# 6_Airframe-NXP_i_MX7.net
KiCad netlist of a schematic drawn in Altium Designer
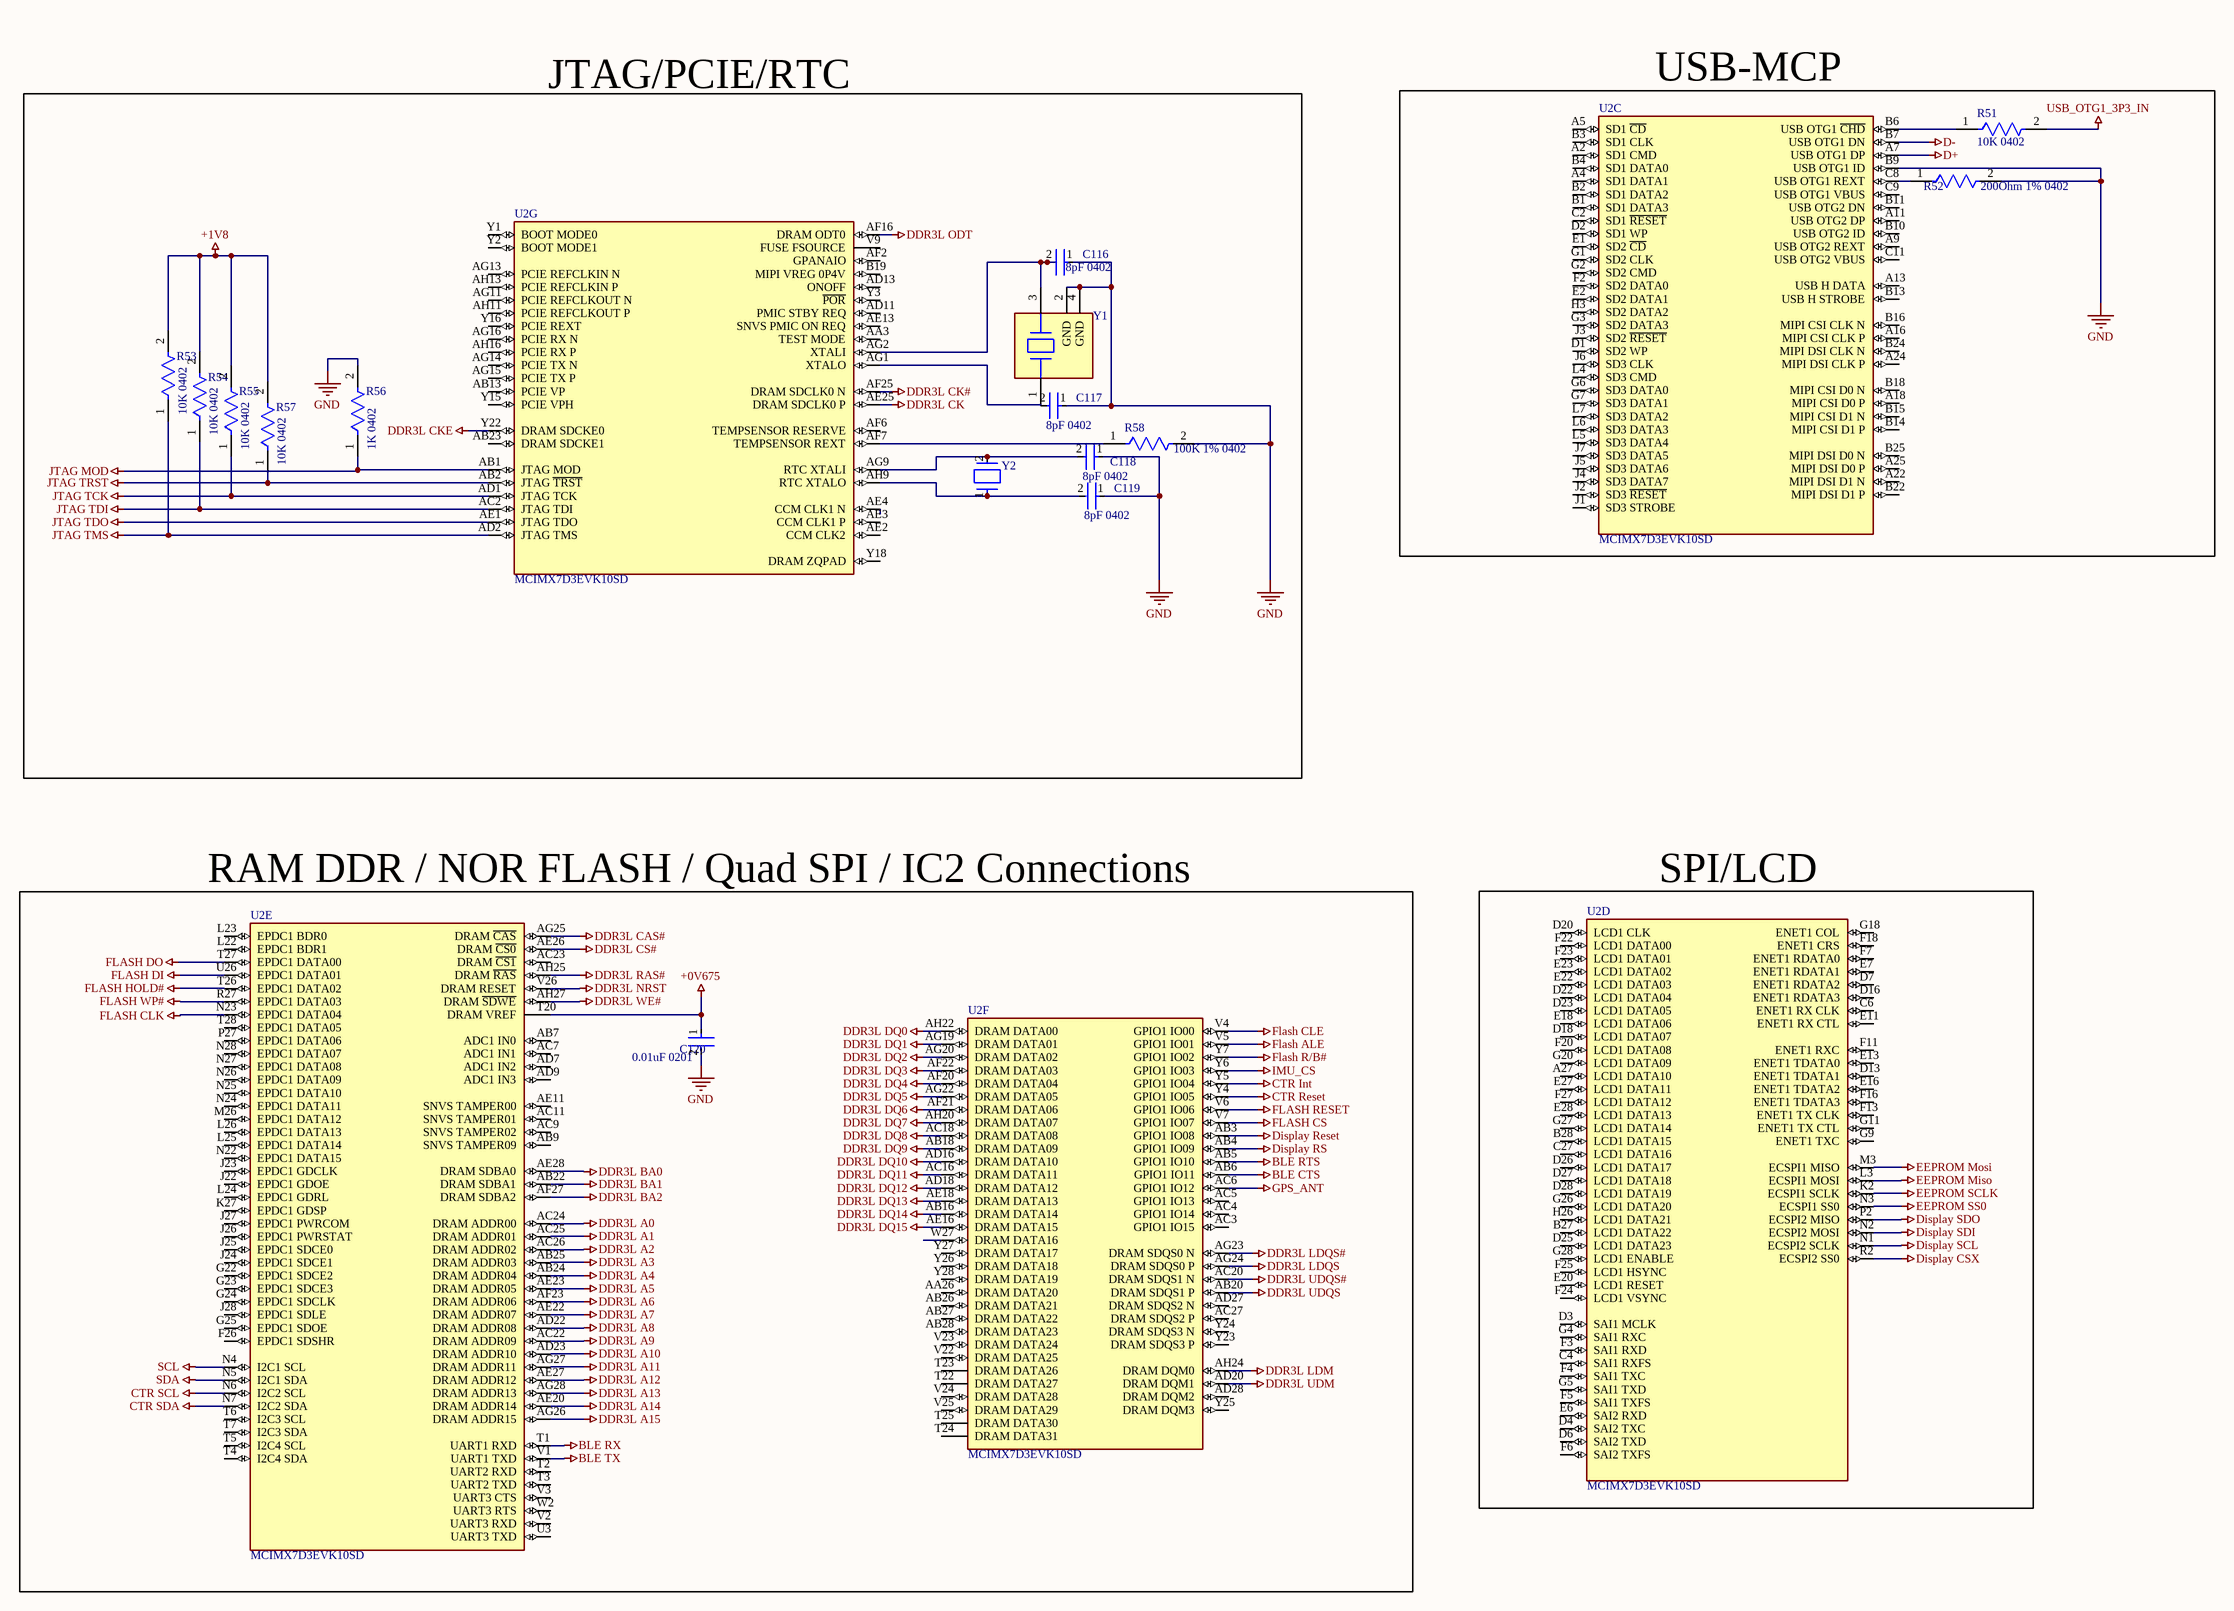
[diagram p0: 6_Airframe-NXP_i.MX7.SchDoc]

(export (version "E")
  (design (tool "Eeschema 10.0.6"))
  (components
    (comp (ref "C116")
      (value "8pF 0402")
      (footprint "FP-C0402C225M9PACTU-MFG")
      (description "CAP CER 2.2UF 6.3V X5R 0402")
      (fields (field (name "VOLTAGE") "6.3V") (field (name "TOLERANCE") "20%"))
      (libsource (lib "Altium Content Vault") (part "b4654b650e69147ec39a6b967a45e02"))
    )
    (comp (ref "C117")
      (value "8pF 0402")
      (footprint "FP-C0402C225M9PACTU-MFG")
      (description "CAP CER 2.2UF 6.3V X5R 0402")
      (fields (field (name "VOLTAGE") "6.3V") (field (name "TOLERANCE") "20%"))
      (libsource (lib "Altium Content Vault") (part "b4654b650e69147ec39a6b967a45e02"))
    )
    (comp (ref "C118")
      (value "8pF 0402")
      (footprint "FP-C0402C225M9PACTU-MFG")
      (description "CAP CER 2.2UF 6.3V X5R 0402")
      (fields (field (name "VOLTAGE") "6.3V") (field (name "TOLERANCE") "20%"))
      (libsource (lib "Altium Content Vault") (part "b4654b650e69147ec39a6b967a45e02"))
    )
    (comp (ref "C119")
      (value "8pF 0402")
      (footprint "FP-C0402C225M9PACTU-MFG")
      (description "CAP CER 2.2UF 6.3V X5R 0402")
      (fields (field (name "VOLTAGE") "6.3V") (field (name "TOLERANCE") "20%"))
      (libsource (lib "Altium Content Vault") (part "b4654b650e69147ec39a6b967a45e02"))
    )
    (comp (ref "C120")
      (value "0.01uF 0201")
      (footprint "FP-C0603-030-0_03-IPC_C")
      (description "Multilayer Ceramic Capacitors 220nF ±10% 6.3V X6S SMD 0201")
      (fields (field (name "TOLERANCE") "10%"))
      (libsource (lib "Altium Content Vault") (part "02cd4be3c70576c341d710602a673aa"))
    )
    (comp (ref "R51")
      (value "10K 0402")
      (footprint "FP-CRCW0402-e3-IPC_B")
      (description "RES SMD 10K OHM 1% 1/16W 0402")
      (fields (field (name "TOLERANCE") "1%"))
      (libsource (lib "Altium Content Vault") (part "1029c3af85768c4190bb7ad29bc67b5"))
    )
    (comp (ref "R52")
      (value "200Ohm 1% 0402")
      (footprint "FP-CRCW0402-e3-IPC_C")
      (description "RES Thick Film, 200Ω, 1%, 0.063W, 100ppm/°C, 0402")
      (fields (field (name "TOLERANCE") "1%"))
      (libsource (lib "Altium Content Vault") (part "1029c3af85768c4190bb7ad29bc67b5"))
    )
    (comp (ref "R53")
      (value "10K 0402")
      (footprint "FP-CRCW0402-e3-IPC_B")
      (description "RES SMD 10K OHM 1% 1/16W 0402")
      (fields (field (name "TOLERANCE") "1%"))
      (libsource (lib "Altium Content Vault") (part "1029c3af85768c4190bb7ad29bc67b5"))
    )
    (comp (ref "R54")
      (value "10K 0402")
      (footprint "FP-CRCW0402-e3-IPC_B")
      (description "RES SMD 10K OHM 1% 1/16W 0402")
      (fields (field (name "TOLERANCE") "1%"))
      (libsource (lib "Altium Content Vault") (part "1029c3af85768c4190bb7ad29bc67b5"))
    )
    (comp (ref "R55")
      (value "10K 0402")
      (footprint "FP-CRCW0402-e3-IPC_B")
      (description "RES SMD 10K OHM 1% 1/16W 0402")
      (fields (field (name "TOLERANCE") "1%"))
      (libsource (lib "Altium Content Vault") (part "1029c3af85768c4190bb7ad29bc67b5"))
    )
    (comp (ref "R56")
      (value "1K 0402")
      (footprint "FP-CRCW0402-e3-IPC_B")
      (description "RES SMD 10K OHM 1% 1/16W 0402")
      (fields (field (name "TOLERANCE") "1%"))
      (libsource (lib "Altium Content Vault") (part "1029c3af85768c4190bb7ad29bc67b5"))
    )
    (comp (ref "R57")
      (value "10K 0402")
      (footprint "FP-CRCW0402-e3-IPC_B")
      (description "RES SMD 10K OHM 1% 1/16W 0402")
      (fields (field (name "TOLERANCE") "1%"))
      (libsource (lib "Altium Content Vault") (part "1029c3af85768c4190bb7ad29bc67b5"))
    )
    (comp (ref "R58")
      (value "100K 1% 0402")
      (footprint "FP-CRCW0402-e3-IPC_C")
      (description "RES Thick Film, 200Ω, 1%, 0.063W, 100ppm/°C, 0402")
      (fields (field (name "TOLERANCE") "1%"))
      (libsource (lib "Altium Content Vault") (part "1029c3af85768c4190bb7ad29bc67b5"))
    )
    (comp (ref "U2")
      (value "MCIMX7D3EVK10SD")
      (footprint "FP-SOT1839-1-IPC_C")
      (description "I.MX 7DUAL: REV 1.3")
      (fields
        (field (name "MANUFACTURER") "NXP")
        (field (name "OCTOPART") "https://octopart.com/mcimx7d3evk10sd-nxp+semiconductors-84356608")
      )
      (libsource (lib "Altium Content Vault") (part "158777adc505239d6b0373594f9eb19"))
    )
    (comp (ref "Y1")
      (value "ABM8AIG-24.000MHZ-12-2Z-T3")
      (footprint "FP-ABM8AIG-MFG")
      (description "Crystal 24MHz ±20ppm (Tol) ±50ppm (Stability) 12pF FUND 50Ω Automotive 4-Pin Ultra Mini-CSMD T/R")
      (libsource (lib "Altium Content Vault") (part "5645ab55de99a04feaa93ac4102b7fe"))
    )
    (comp (ref "Y2")
      (value "ABS06-32.768KHZ-9-T")
      (footprint "FP-ABS06-MFG")
      (description "Crystal 32.768kHz ±20ppm (Tol) 9pF FUND 90kΩ 2-Pin Mini-CSMD T/R")
      (fields (field (name "TOLERANCE") "20ppm"))
      (libsource (lib "Altium Content Vault") (part "c23a69dc6c9e2f18f2079038eb95dd1"))
    )
  )
  (nets
    (net (code "1") (name "+0V675") (class "Default")
      (node (ref "C120") (pin "1") (pinfunction "1_1") (pintype "passive"))
      (node (ref "U2") (pin "T20") (pinfunction "DRAM_VREF_T20") (pintype "power_in"))
    )
    (net (code "2") (name "+1V8") (class "Default")
      (node (ref "R53") (pin "2") (pinfunction "2_2") (pintype "passive"))
      (node (ref "R54") (pin "2") (pinfunction "2_2") (pintype "passive"))
      (node (ref "R55") (pin "2") (pinfunction "2_2") (pintype "passive"))
      (node (ref "R57") (pin "2") (pinfunction "2_2") (pintype "passive"))
    )
    (net (code "3") (name "BLE CTS") (class "Default")
      (node (ref "U2") (pin "AB6") (pinfunction "GPIO1_IO11_AB6") (pintype "bidirectional"))
    )
    (net (code "4") (name "BLE RTS") (class "Default")
      (node (ref "U2") (pin "AB5") (pinfunction "GPIO1_IO10_AB5") (pintype "bidirectional"))
    )
    (net (code "5") (name "BLE RX") (class "Default")
      (node (ref "U2") (pin "T1") (pinfunction "UART1_RXD_T1") (pintype "bidirectional"))
    )
    (net (code "6") (name "BLE TX") (class "Default")
      (node (ref "U2") (pin "V1") (pinfunction "UART1_TXD_V1") (pintype "bidirectional"))
    )
    (net (code "7") (name "CTR Int") (class "Default")
      (node (ref "U2") (pin "Y5") (pinfunction "GPIO1_IO04_Y5") (pintype "bidirectional"))
    )
    (net (code "8") (name "CTR Reset") (class "Default")
      (node (ref "U2") (pin "Y4") (pinfunction "GPIO1_IO05_Y4") (pintype "bidirectional"))
    )
    (net (code "9") (name "CTR SCL") (class "Default")
      (node (ref "U2") (pin "N6") (pinfunction "I2C2_SCL_N6") (pintype "bidirectional"))
    )
    (net (code "10") (name "CTR SDA") (class "Default")
      (node (ref "U2") (pin "N7") (pinfunction "I2C2_SDA_N7") (pintype "bidirectional"))
    )
    (net (code "11") (name "D+") (class "Default")
      (node (ref "U2") (pin "A7") (pinfunction "USB_OTG1_DP_A7") (pintype "bidirectional"))
    )
    (net (code "12") (name "D-") (class "Default")
      (node (ref "U2") (pin "B7") (pinfunction "USB_OTG1_DN_B7") (pintype "bidirectional"))
    )
    (net (code "13") (name "DDR3L A0") (class "Default")
      (node (ref "U2") (pin "AC24") (pinfunction "DRAM_ADDR00_AC24") (pintype "bidirectional"))
    )
    (net (code "14") (name "DDR3L A1") (class "Default")
      (node (ref "U2") (pin "AC25") (pinfunction "DRAM_ADDR01_AC25") (pintype "bidirectional"))
    )
    (net (code "15") (name "DDR3L A2") (class "Default")
      (node (ref "U2") (pin "AC26") (pinfunction "DRAM_ADDR02_AC26") (pintype "bidirectional"))
    )
    (net (code "16") (name "DDR3L A3") (class "Default")
      (node (ref "U2") (pin "AB25") (pinfunction "DRAM_ADDR03_AB25") (pintype "bidirectional"))
    )
    (net (code "17") (name "DDR3L A4") (class "Default")
      (node (ref "U2") (pin "AB24") (pinfunction "DRAM_ADDR04_AB24") (pintype "bidirectional"))
    )
    (net (code "18") (name "DDR3L A5") (class "Default")
      (node (ref "U2") (pin "AE23") (pinfunction "DRAM_ADDR05_AE23") (pintype "bidirectional"))
    )
    (net (code "19") (name "DDR3L A6") (class "Default")
      (node (ref "U2") (pin "AF23") (pinfunction "DRAM_ADDR06_AF23") (pintype "bidirectional"))
    )
    (net (code "20") (name "DDR3L A7") (class "Default")
      (node (ref "U2") (pin "AE22") (pinfunction "DRAM_ADDR07_AE22") (pintype "bidirectional"))
    )
    (net (code "21") (name "DDR3L A8") (class "Default")
      (node (ref "U2") (pin "AD22") (pinfunction "DRAM_ADDR08_AD22") (pintype "bidirectional"))
    )
    (net (code "22") (name "DDR3L A9") (class "Default")
      (node (ref "U2") (pin "AC22") (pinfunction "DRAM_ADDR09_AC22") (pintype "bidirectional"))
    )
    (net (code "23") (name "DDR3L A10") (class "Default")
      (node (ref "U2") (pin "AD23") (pinfunction "DRAM_ADDR10_AD23") (pintype "bidirectional"))
    )
    (net (code "24") (name "DDR3L A11") (class "Default")
      (node (ref "U2") (pin "AG27") (pinfunction "DRAM_ADDR11_AG27") (pintype "bidirectional"))
    )
    (net (code "25") (name "DDR3L A12") (class "Default")
      (node (ref "U2") (pin "AE27") (pinfunction "DRAM_ADDR12_AE27") (pintype "bidirectional"))
    )
    (net (code "26") (name "DDR3L A13") (class "Default")
      (node (ref "U2") (pin "AG28") (pinfunction "DRAM_ADDR13_AG28") (pintype "bidirectional"))
    )
    (net (code "27") (name "DDR3L A14") (class "Default")
      (node (ref "U2") (pin "AE20") (pinfunction "DRAM_ADDR14_AE20") (pintype "bidirectional"))
    )
    (net (code "28") (name "DDR3L A15") (class "Default")
      (node (ref "U2") (pin "AG26") (pinfunction "DRAM_ADDR15_AG26") (pintype "bidirectional"))
    )
    (net (code "29") (name "DDR3L BA0") (class "Default")
      (node (ref "U2") (pin "AE28") (pinfunction "DRAM_SDBA0_AE28") (pintype "bidirectional"))
    )
    (net (code "30") (name "DDR3L BA1") (class "Default")
      (node (ref "U2") (pin "AB22") (pinfunction "DRAM_SDBA1_AB22") (pintype "bidirectional"))
    )
    (net (code "31") (name "DDR3L BA2") (class "Default")
      (node (ref "U2") (pin "AF27") (pinfunction "DRAM_SDBA2_AF27") (pintype "bidirectional"))
    )
    (net (code "32") (name "DDR3L CAS#") (class "Default")
      (node (ref "U2") (pin "AG25") (pinfunction "DRAM_~{CAS}_AG25") (pintype "bidirectional"))
    )
    (net (code "33") (name "DDR3L CK") (class "Default")
      (node (ref "U2") (pin "AE25") (pinfunction "DRAM_SDCLK0_P_AE25") (pintype "bidirectional"))
    )
    (net (code "34") (name "DDR3L CK#") (class "Default")
      (node (ref "U2") (pin "AF25") (pinfunction "DRAM_SDCLK0_N_AF25") (pintype "bidirectional"))
    )
    (net (code "35") (name "DDR3L CKE") (class "Default")
      (node (ref "U2") (pin "Y22") (pinfunction "DRAM_SDCKE0_Y22") (pintype "bidirectional"))
    )
    (net (code "36") (name "DDR3L CS#") (class "Default")
      (node (ref "U2") (pin "AE26") (pinfunction "DRAM_~{CS0}_AE26") (pintype "bidirectional"))
    )
    (net (code "37") (name "DDR3L DQ0") (class "Default")
      (node (ref "U2") (pin "AH22") (pinfunction "DRAM_DATA00_AH22") (pintype "bidirectional"))
    )
    (net (code "38") (name "DDR3L DQ1") (class "Default")
      (node (ref "U2") (pin "AG19") (pinfunction "DRAM_DATA01_AG19") (pintype "bidirectional"))
    )
    (net (code "39") (name "DDR3L DQ2") (class "Default")
      (node (ref "U2") (pin "AG20") (pinfunction "DRAM_DATA02_AG20") (pintype "bidirectional"))
    )
    (net (code "40") (name "DDR3L DQ3") (class "Default")
      (node (ref "U2") (pin "AF22") (pinfunction "DRAM_DATA03_AF22") (pintype "bidirectional"))
    )
    (net (code "41") (name "DDR3L DQ4") (class "Default")
      (node (ref "U2") (pin "AF20") (pinfunction "DRAM_DATA04_AF20") (pintype "bidirectional"))
    )
    (net (code "42") (name "DDR3L DQ5") (class "Default")
      (node (ref "U2") (pin "AG22") (pinfunction "DRAM_DATA05_AG22") (pintype "bidirectional"))
    )
    (net (code "43") (name "DDR3L DQ6") (class "Default")
      (node (ref "U2") (pin "AF21") (pinfunction "DRAM_DATA06_AF21") (pintype "bidirectional"))
    )
    (net (code "44") (name "DDR3L DQ7") (class "Default")
      (node (ref "U2") (pin "AH20") (pinfunction "DRAM_DATA07_AH20") (pintype "bidirectional"))
    )
    (net (code "45") (name "DDR3L DQ8") (class "Default")
      (node (ref "U2") (pin "AC18") (pinfunction "DRAM_DATA08_AC18") (pintype "bidirectional"))
    )
    (net (code "46") (name "DDR3L DQ9") (class "Default")
      (node (ref "U2") (pin "AB18") (pinfunction "DRAM_DATA09_AB18") (pintype "bidirectional"))
    )
    (net (code "47") (name "DDR3L DQ10") (class "Default")
      (node (ref "U2") (pin "AD16") (pinfunction "DRAM_DATA10_AD16") (pintype "bidirectional"))
    )
    (net (code "48") (name "DDR3L DQ11") (class "Default")
      (node (ref "U2") (pin "AC16") (pinfunction "DRAM_DATA11_AC16") (pintype "bidirectional"))
    )
    (net (code "49") (name "DDR3L DQ12") (class "Default")
      (node (ref "U2") (pin "AD18") (pinfunction "DRAM_DATA12_AD18") (pintype "bidirectional"))
    )
    (net (code "50") (name "DDR3L DQ13") (class "Default")
      (node (ref "U2") (pin "AE18") (pinfunction "DRAM_DATA13_AE18") (pintype "bidirectional"))
    )
    (net (code "51") (name "DDR3L DQ14") (class "Default")
      (node (ref "U2") (pin "AB16") (pinfunction "DRAM_DATA14_AB16") (pintype "bidirectional"))
    )
    (net (code "52") (name "DDR3L DQ15") (class "Default")
      (node (ref "U2") (pin "AE16") (pinfunction "DRAM_DATA15_AE16") (pintype "bidirectional"))
    )
    (net (code "53") (name "DDR3L LDM") (class "Default")
      (node (ref "U2") (pin "AH24") (pinfunction "DRAM_DQM0_AH24") (pintype "bidirectional"))
    )
    (net (code "54") (name "DDR3L LDQS") (class "Default")
      (node (ref "U2") (pin "AG24") (pinfunction "DRAM_SDQS0_P_AG24") (pintype "bidirectional"))
    )
    (net (code "55") (name "DDR3L LDQS#") (class "Default")
      (node (ref "U2") (pin "AG23") (pinfunction "DRAM_SDQS0_N_AG23") (pintype "bidirectional"))
    )
    (net (code "56") (name "DDR3L NRST") (class "Default")
      (node (ref "U2") (pin "V26") (pinfunction "DRAM_RESET_V26") (pintype "bidirectional"))
    )
    (net (code "57") (name "DDR3L ODT") (class "Default")
      (node (ref "U2") (pin "AF16") (pinfunction "DRAM_ODT0_AF16") (pintype "bidirectional"))
    )
    (net (code "58") (name "DDR3L RAS#") (class "Default")
      (node (ref "U2") (pin "AH25") (pinfunction "DRAM_~{RAS}_AH25") (pintype "bidirectional"))
    )
    (net (code "59") (name "DDR3L UDM") (class "Default")
      (node (ref "U2") (pin "AD20") (pinfunction "DRAM_DQM1_AD20") (pintype "bidirectional"))
    )
    (net (code "60") (name "DDR3L UDQS") (class "Default")
      (node (ref "U2") (pin "AB20") (pinfunction "DRAM_SDQS1_P_AB20") (pintype "bidirectional"))
    )
    (net (code "61") (name "DDR3L UDQS#") (class "Default")
      (node (ref "U2") (pin "AC20") (pinfunction "DRAM_SDQS1_N_AC20") (pintype "bidirectional"))
    )
    (net (code "62") (name "DDR3L WE#") (class "Default")
      (node (ref "U2") (pin "AH27") (pinfunction "DRAM_~{SDWE}_AH27") (pintype "bidirectional"))
    )
    (net (code "63") (name "Display CSX") (class "Default")
      (node (ref "U2") (pin "R2") (pinfunction "ECSPI2_SS0_R2") (pintype "bidirectional"))
    )
    (net (code "64") (name "Display RS") (class "Default")
      (node (ref "U2") (pin "AB4") (pinfunction "GPIO1_IO09_AB4") (pintype "bidirectional"))
    )
    (net (code "65") (name "Display Reset") (class "Default")
      (node (ref "U2") (pin "AB3") (pinfunction "GPIO1_IO08_AB3") (pintype "bidirectional"))
    )
    (net (code "66") (name "Display SCL") (class "Default")
      (node (ref "U2") (pin "N1") (pinfunction "ECSPI2_SCLK_N1") (pintype "bidirectional"))
    )
    (net (code "67") (name "Display SDI") (class "Default")
      (node (ref "U2") (pin "N2") (pinfunction "ECSPI2_MOSI_N2") (pintype "bidirectional"))
    )
    (net (code "68") (name "Display SDO") (class "Default")
      (node (ref "U2") (pin "P2") (pinfunction "ECSPI2_MISO_P2") (pintype "bidirectional"))
    )
    (net (code "69") (name "EEPROM Miso") (class "Default")
      (node (ref "U2") (pin "L3") (pinfunction "ECSPI1_MOSI_L3") (pintype "bidirectional"))
    )
    (net (code "70") (name "EEPROM Mosi") (class "Default")
      (node (ref "U2") (pin "M3") (pinfunction "ECSPI1_MISO_M3") (pintype "bidirectional"))
    )
    (net (code "71") (name "EEPROM SCLK") (class "Default")
      (node (ref "U2") (pin "K2") (pinfunction "ECSPI1_SCLK_K2") (pintype "bidirectional"))
    )
    (net (code "72") (name "EEPROM SS0") (class "Default")
      (node (ref "U2") (pin "N3") (pinfunction "ECSPI1_SS0_N3") (pintype "bidirectional"))
    )
    (net (code "73") (name "FLASH CLK") (class "Default")
      (node (ref "U2") (pin "N23") (pinfunction "EPDC1_DATA04_N23") (pintype "bidirectional"))
    )
    (net (code "74") (name "FLASH CS") (class "Default")
      (node (ref "U2") (pin "V7") (pinfunction "GPIO1_IO07_V7") (pintype "bidirectional"))
    )
    (net (code "75") (name "FLASH DI") (class "Default")
      (node (ref "U2") (pin "U26") (pinfunction "EPDC1_DATA01_U26") (pintype "bidirectional"))
    )
    (net (code "76") (name "FLASH DO") (class "Default")
      (node (ref "U2") (pin "T27") (pinfunction "EPDC1_DATA00_T27") (pintype "bidirectional"))
    )
    (net (code "77") (name "FLASH HOLD#") (class "Default")
      (node (ref "U2") (pin "T26") (pinfunction "EPDC1_DATA02_T26") (pintype "bidirectional"))
    )
    (net (code "78") (name "FLASH RESET") (class "Default")
      (node (ref "U2") (pin "V6") (pinfunction "GPIO1_IO06_V6") (pintype "bidirectional"))
    )
    (net (code "79") (name "FLASH WP#") (class "Default")
      (node (ref "U2") (pin "R27") (pinfunction "EPDC1_DATA03_R27") (pintype "bidirectional"))
    )
    (net (code "80") (name "Flash ALE") (class "Default")
      (node (ref "U2") (pin "V5") (pinfunction "GPIO1_IO01_V5") (pintype "bidirectional"))
    )
    (net (code "81") (name "Flash CLE") (class "Default")
      (node (ref "U2") (pin "V4") (pinfunction "GPIO1_IO00_V4") (pintype "bidirectional"))
    )
    (net (code "82") (name "Flash R{slash}B#") (class "Default")
      (node (ref "U2") (pin "Y7") (pinfunction "GPIO1_IO02_Y7") (pintype "bidirectional"))
    )
    (net (code "83") (name "GND") (class "Default")
      (node (ref "C116") (pin "1") (pinfunction "1_1") (pintype "passive"))
      (node (ref "C117") (pin "1") (pinfunction "1_1") (pintype "passive"))
      (node (ref "C118") (pin "1") (pinfunction "1_1") (pintype "passive"))
      (node (ref "C119") (pin "1") (pinfunction "1_1") (pintype "passive"))
      (node (ref "C120") (pin "2") (pinfunction "2_2") (pintype "passive"))
      (node (ref "R52") (pin "2") (pinfunction "2_2") (pintype "passive"))
      (node (ref "R56") (pin "2") (pinfunction "2_2") (pintype "passive"))
      (node (ref "R58") (pin "2") (pinfunction "2_2") (pintype "passive"))
      (node (ref "U2") (pin "B9") (pinfunction "USB_OTG1_ID_B9") (pintype "bidirectional"))
      (node (ref "Y1") (pin "2") (pinfunction "GND_2") (pintype "power_in"))
      (node (ref "Y1") (pin "4") (pinfunction "GND_4") (pintype "power_in"))
    )
    (net (code "84") (name "GPS_ANT") (class "Default")
      (node (ref "U2") (pin "AC6") (pinfunction "GPIO1_IO12_AC6") (pintype "bidirectional"))
    )
    (net (code "85") (name "IMU_CS") (class "Default")
      (node (ref "U2") (pin "Y6") (pinfunction "GPIO1_IO03_Y6") (pintype "bidirectional"))
    )
    (net (code "86") (name "JTAG MOD") (class "Default")
      (node (ref "R56") (pin "1") (pinfunction "1_1") (pintype "passive"))
      (node (ref "U2") (pin "AB1") (pinfunction "JTAG_MOD_AB1") (pintype "bidirectional"))
    )
    (net (code "87") (name "JTAG TCK") (class "Default")
      (node (ref "R55") (pin "1") (pinfunction "1_1") (pintype "passive"))
      (node (ref "U2") (pin "AD1") (pinfunction "JTAG_TCK_AD1") (pintype "bidirectional"))
    )
    (net (code "88") (name "JTAG TDI") (class "Default")
      (node (ref "R54") (pin "1") (pinfunction "1_1") (pintype "passive"))
      (node (ref "U2") (pin "AC2") (pinfunction "JTAG_TDI_AC2") (pintype "bidirectional"))
    )
    (net (code "89") (name "JTAG TDO") (class "Default")
      (node (ref "U2") (pin "AE1") (pinfunction "JTAG_TDO_AE1") (pintype "bidirectional"))
    )
    (net (code "90") (name "JTAG TMS") (class "Default")
      (node (ref "R53") (pin "1") (pinfunction "1_1") (pintype "passive"))
      (node (ref "U2") (pin "AD2") (pinfunction "JTAG_TMS_AD2") (pintype "bidirectional"))
    )
    (net (code "91") (name "JTAG TRST") (class "Default")
      (node (ref "R57") (pin "1") (pinfunction "1_1") (pintype "passive"))
      (node (ref "U2") (pin "AB2") (pinfunction "JTAG_~{TRST}_AB2") (pintype "bidirectional"))
    )
    (net (code "92") (name "Net-(U2C-USB_OTG1_REXT)") (class "Default")
      (node (ref "R52") (pin "1") (pinfunction "1_1") (pintype "passive"))
      (node (ref "U2") (pin "C8") (pinfunction "USB_OTG1_REXT_C8") (pintype "bidirectional"))
    )
    (net (code "93") (name "Net-(U2C-USB_OTG1_~{CHD})") (class "Default")
      (node (ref "R51") (pin "1") (pinfunction "1_1") (pintype "passive"))
      (node (ref "U2") (pin "B6") (pinfunction "USB_OTG1_~{CHD}_B6") (pintype "bidirectional"))
    )
    (net (code "94") (name "Net-(U2G-RTC_XTALI)") (class "Default")
      (node (ref "C118") (pin "2") (pinfunction "2_2") (pintype "passive"))
      (node (ref "U2") (pin "AG9") (pinfunction "RTC_XTALI_AG9") (pintype "bidirectional"))
      (node (ref "Y2") (pin "2") (pinfunction "2_2") (pintype "passive"))
    )
    (net (code "95") (name "Net-(U2G-RTC_XTALO)") (class "Default")
      (node (ref "C119") (pin "2") (pinfunction "2_2") (pintype "passive"))
      (node (ref "U2") (pin "AH9") (pinfunction "RTC_XTALO_AH9") (pintype "bidirectional"))
      (node (ref "Y2") (pin "1") (pinfunction "1_1") (pintype "passive"))
    )
    (net (code "96") (name "Net-(U2G-TEMPSENSOR_REXT)") (class "Default")
      (node (ref "R58") (pin "1") (pinfunction "1_1") (pintype "passive"))
      (node (ref "U2") (pin "AF7") (pinfunction "TEMPSENSOR_REXT_AF7") (pintype "bidirectional"))
    )
    (net (code "97") (name "Net-(U2G-XTALI)") (class "Default")
      (node (ref "C116") (pin "2") (pinfunction "2_2") (pintype "passive"))
      (node (ref "U2") (pin "AG2") (pinfunction "XTALI_AG2") (pintype "bidirectional"))
      (node (ref "Y1") (pin "3") (pinfunction "3_3") (pintype "passive"))
    )
    (net (code "98") (name "Net-(U2G-XTALO)") (class "Default")
      (node (ref "U2") (pin "AG1") (pinfunction "XTALO_AG1") (pintype "bidirectional"))
      (node (ref "Y1") (pin "1") (pinfunction "1_1") (pintype "passive"))
    )
    (net (code "99") (name "SCL") (class "Default")
      (node (ref "U2") (pin "N4") (pinfunction "I2C1_SCL_N4") (pintype "bidirectional"))
    )
    (net (code "100") (name "SDA") (class "Default")
      (node (ref "U2") (pin "N5") (pinfunction "I2C1_SDA_N5") (pintype "bidirectional"))
    )
    (net (code "101") (name "USB_OTG1_3P3_IN") (class "Default")
      (node (ref "R51") (pin "2") (pinfunction "2_2") (pintype "passive"))
    )
    (net (code "102") (name "unconnected-(C117-Pad2)") (class "Default")
      (node (ref "C117") (pin "2") (pinfunction "2_2") (pintype "passive"))
    )
    (net (code "103") (name "unconnected-(U2C-MIPI_CSI_CLK_N-PadB16)") (class "Default")
      (node (ref "U2") (pin "B16") (pinfunction "MIPI_CSI_CLK_N_B16") (pintype "bidirectional"))
    )
    (net (code "104") (name "unconnected-(U2C-MIPI_CSI_CLK_P-PadA16)") (class "Default")
      (node (ref "U2") (pin "A16") (pinfunction "MIPI_CSI_CLK_P_A16") (pintype "bidirectional"))
    )
    (net (code "105") (name "unconnected-(U2C-MIPI_CSI_D0_N-PadB18)") (class "Default")
      (node (ref "U2") (pin "B18") (pinfunction "MIPI_CSI_D0_N_B18") (pintype "bidirectional"))
    )
    (net (code "106") (name "unconnected-(U2C-MIPI_CSI_D0_P-PadA18)") (class "Default")
      (node (ref "U2") (pin "A18") (pinfunction "MIPI_CSI_D0_P_A18") (pintype "bidirectional"))
    )
    (net (code "107") (name "unconnected-(U2C-MIPI_CSI_D1_N-PadB15)") (class "Default")
      (node (ref "U2") (pin "B15") (pinfunction "MIPI_CSI_D1_N_B15") (pintype "bidirectional"))
    )
    (net (code "108") (name "unconnected-(U2C-MIPI_CSI_D1_P-PadB14)") (class "Default")
      (node (ref "U2") (pin "B14") (pinfunction "MIPI_CSI_D1_P_B14") (pintype "bidirectional"))
    )
    (net (code "109") (name "unconnected-(U2C-MIPI_DSI_CLK_N-PadB24)") (class "Default")
      (node (ref "U2") (pin "B24") (pinfunction "MIPI_DSI_CLK_N_B24") (pintype "bidirectional"))
    )
    (net (code "110") (name "unconnected-(U2C-MIPI_DSI_CLK_P-PadA24)") (class "Default")
      (node (ref "U2") (pin "A24") (pinfunction "MIPI_DSI_CLK_P_A24") (pintype "bidirectional"))
    )
    (net (code "111") (name "unconnected-(U2C-MIPI_DSI_D0_N-PadB25)") (class "Default")
      (node (ref "U2") (pin "B25") (pinfunction "MIPI_DSI_D0_N_B25") (pintype "bidirectional"))
    )
    (net (code "112") (name "unconnected-(U2C-MIPI_DSI_D0_P-PadA25)") (class "Default")
      (node (ref "U2") (pin "A25") (pinfunction "MIPI_DSI_D0_P_A25") (pintype "bidirectional"))
    )
    (net (code "113") (name "unconnected-(U2C-MIPI_DSI_D1_N-PadA22)") (class "Default")
      (node (ref "U2") (pin "A22") (pinfunction "MIPI_DSI_D1_N_A22") (pintype "bidirectional"))
    )
    (net (code "114") (name "unconnected-(U2C-MIPI_DSI_D1_P-PadB22)") (class "Default")
      (node (ref "U2") (pin "B22") (pinfunction "MIPI_DSI_D1_P_B22") (pintype "bidirectional"))
    )
    (net (code "115") (name "unconnected-(U2C-SD1_CLK-PadB3)") (class "Default")
      (node (ref "U2") (pin "B3") (pinfunction "SD1_CLK_B3") (pintype "bidirectional"))
    )
    (net (code "116") (name "unconnected-(U2C-SD1_CMD-PadA2)") (class "Default")
      (node (ref "U2") (pin "A2") (pinfunction "SD1_CMD_A2") (pintype "bidirectional"))
    )
    (net (code "117") (name "unconnected-(U2C-SD1_DATA0-PadB4)") (class "Default")
      (node (ref "U2") (pin "B4") (pinfunction "SD1_DATA0_B4") (pintype "bidirectional"))
    )
    (net (code "118") (name "unconnected-(U2C-SD1_DATA1-PadA4)") (class "Default")
      (node (ref "U2") (pin "A4") (pinfunction "SD1_DATA1_A4") (pintype "bidirectional"))
    )
    (net (code "119") (name "unconnected-(U2C-SD1_DATA2-PadB2)") (class "Default")
      (node (ref "U2") (pin "B2") (pinfunction "SD1_DATA2_B2") (pintype "bidirectional"))
    )
    (net (code "120") (name "unconnected-(U2C-SD1_DATA3-PadB1)") (class "Default")
      (node (ref "U2") (pin "B1") (pinfunction "SD1_DATA3_B1") (pintype "bidirectional"))
    )
    (net (code "121") (name "unconnected-(U2C-SD1_WP-PadD2)") (class "Default")
      (node (ref "U2") (pin "D2") (pinfunction "SD1_WP_D2") (pintype "bidirectional"))
    )
    (net (code "122") (name "unconnected-(U2C-SD1_~{CD}-PadA5)") (class "Default")
      (node (ref "U2") (pin "A5") (pinfunction "SD1_~{CD}_A5") (pintype "bidirectional"))
    )
    (net (code "123") (name "unconnected-(U2C-SD1_~{RESET}-PadC2)") (class "Default")
      (node (ref "U2") (pin "C2") (pinfunction "SD1_~{RESET}_C2") (pintype "bidirectional"))
    )
    (net (code "124") (name "unconnected-(U2C-SD2_CLK-PadG1)") (class "Default")
      (node (ref "U2") (pin "G1") (pinfunction "SD2_CLK_G1") (pintype "bidirectional"))
    )
    (net (code "125") (name "unconnected-(U2C-SD2_CMD-PadG2)") (class "Default")
      (node (ref "U2") (pin "G2") (pinfunction "SD2_CMD_G2") (pintype "bidirectional"))
    )
    (net (code "126") (name "unconnected-(U2C-SD2_DATA0-PadF2)") (class "Default")
      (node (ref "U2") (pin "F2") (pinfunction "SD2_DATA0_F2") (pintype "bidirectional"))
    )
    (net (code "127") (name "unconnected-(U2C-SD2_DATA1-PadE2)") (class "Default")
      (node (ref "U2") (pin "E2") (pinfunction "SD2_DATA1_E2") (pintype "bidirectional"))
    )
    (net (code "128") (name "unconnected-(U2C-SD2_DATA2-PadH3)") (class "Default")
      (node (ref "U2") (pin "H3") (pinfunction "SD2_DATA2_H3") (pintype "bidirectional"))
    )
    (net (code "129") (name "unconnected-(U2C-SD2_DATA3-PadG3)") (class "Default")
      (node (ref "U2") (pin "G3") (pinfunction "SD2_DATA3_G3") (pintype "bidirectional"))
    )
    (net (code "130") (name "unconnected-(U2C-SD2_WP-PadD1)") (class "Default")
      (node (ref "U2") (pin "D1") (pinfunction "SD2_WP_D1") (pintype "bidirectional"))
    )
    (net (code "131") (name "unconnected-(U2C-SD2_~{CD}-PadE1)") (class "Default")
      (node (ref "U2") (pin "E1") (pinfunction "SD2_~{CD}_E1") (pintype "bidirectional"))
    )
    (net (code "132") (name "unconnected-(U2C-SD2_~{RESET}-PadJ3)") (class "Default")
      (node (ref "U2") (pin "J3") (pinfunction "SD2_~{RESET}_J3") (pintype "bidirectional"))
    )
    (net (code "133") (name "unconnected-(U2C-SD3_CLK-PadJ6)") (class "Default")
      (node (ref "U2") (pin "J6") (pinfunction "SD3_CLK_J6") (pintype "bidirectional"))
    )
    (net (code "134") (name "unconnected-(U2C-SD3_CMD-PadL4)") (class "Default")
      (node (ref "U2") (pin "L4") (pinfunction "SD3_CMD_L4") (pintype "bidirectional"))
    )
    (net (code "135") (name "unconnected-(U2C-SD3_DATA0-PadG6)") (class "Default")
      (node (ref "U2") (pin "G6") (pinfunction "SD3_DATA0_G6") (pintype "bidirectional"))
    )
    (net (code "136") (name "unconnected-(U2C-SD3_DATA1-PadG7)") (class "Default")
      (node (ref "U2") (pin "G7") (pinfunction "SD3_DATA1_G7") (pintype "bidirectional"))
    )
    (net (code "137") (name "unconnected-(U2C-SD3_DATA2-PadL7)") (class "Default")
      (node (ref "U2") (pin "L7") (pinfunction "SD3_DATA2_L7") (pintype "bidirectional"))
    )
    (net (code "138") (name "unconnected-(U2C-SD3_DATA3-PadL6)") (class "Default")
      (node (ref "U2") (pin "L6") (pinfunction "SD3_DATA3_L6") (pintype "bidirectional"))
    )
    (net (code "139") (name "unconnected-(U2C-SD3_DATA4-PadL5)") (class "Default")
      (node (ref "U2") (pin "L5") (pinfunction "SD3_DATA4_L5") (pintype "bidirectional"))
    )
    (net (code "140") (name "unconnected-(U2C-SD3_DATA5-PadJ7)") (class "Default")
      (node (ref "U2") (pin "J7") (pinfunction "SD3_DATA5_J7") (pintype "bidirectional"))
    )
    (net (code "141") (name "unconnected-(U2C-SD3_DATA6-PadJ5)") (class "Default")
      (node (ref "U2") (pin "J5") (pinfunction "SD3_DATA6_J5") (pintype "bidirectional"))
    )
    (net (code "142") (name "unconnected-(U2C-SD3_DATA7-PadJ4)") (class "Default")
      (node (ref "U2") (pin "J4") (pinfunction "SD3_DATA7_J4") (pintype "bidirectional"))
    )
    (net (code "143") (name "unconnected-(U2C-SD3_STROBE-PadJ1)") (class "Default")
      (node (ref "U2") (pin "J1") (pinfunction "SD3_STROBE_J1") (pintype "bidirectional"))
    )
    (net (code "144") (name "unconnected-(U2C-SD3_~{RESET}-PadJ2)") (class "Default")
      (node (ref "U2") (pin "J2") (pinfunction "SD3_~{RESET}_J2") (pintype "bidirectional"))
    )
    (net (code "145") (name "unconnected-(U2C-USB_H_DATA-PadA13)") (class "Default")
      (node (ref "U2") (pin "A13") (pinfunction "USB_H_DATA_A13") (pintype "bidirectional"))
    )
    (net (code "146") (name "unconnected-(U2C-USB_H_STROBE-PadB13)") (class "Default")
      (node (ref "U2") (pin "B13") (pinfunction "USB_H_STROBE_B13") (pintype "bidirectional"))
    )
    (net (code "147") (name "unconnected-(U2C-USB_OTG1_VBUS-PadC9)") (class "Default")
      (node (ref "U2") (pin "C9") (pinfunction "USB_OTG1_VBUS_C9") (pintype "bidirectional"))
    )
    (net (code "148") (name "unconnected-(U2C-USB_OTG2_DN-PadB11)") (class "Default")
      (node (ref "U2") (pin "B11") (pinfunction "USB_OTG2_DN_B11") (pintype "bidirectional"))
    )
    (net (code "149") (name "unconnected-(U2C-USB_OTG2_DP-PadA11)") (class "Default")
      (node (ref "U2") (pin "A11") (pinfunction "USB_OTG2_DP_A11") (pintype "bidirectional"))
    )
    (net (code "150") (name "unconnected-(U2C-USB_OTG2_ID-PadB10)") (class "Default")
      (node (ref "U2") (pin "B10") (pinfunction "USB_OTG2_ID_B10") (pintype "bidirectional"))
    )
    (net (code "151") (name "unconnected-(U2C-USB_OTG2_REXT-PadA9)") (class "Default")
      (node (ref "U2") (pin "A9") (pinfunction "USB_OTG2_REXT_A9") (pintype "bidirectional"))
    )
    (net (code "152") (name "unconnected-(U2C-USB_OTG2_VBUS-PadC11)") (class "Default")
      (node (ref "U2") (pin "C11") (pinfunction "USB_OTG2_VBUS_C11") (pintype "bidirectional"))
    )
    (net (code "153") (name "unconnected-(U2D-ENET1_COL-PadG18)") (class "Default")
      (node (ref "U2") (pin "G18") (pinfunction "ENET1_COL_G18") (pintype "bidirectional"))
    )
    (net (code "154") (name "unconnected-(U2D-ENET1_CRS-PadF18)") (class "Default")
      (node (ref "U2") (pin "F18") (pinfunction "ENET1_CRS_F18") (pintype "bidirectional"))
    )
    (net (code "155") (name "unconnected-(U2D-ENET1_RDATA0-PadF7)") (class "Default")
      (node (ref "U2") (pin "F7") (pinfunction "ENET1_RDATA0_F7") (pintype "bidirectional"))
    )
    (net (code "156") (name "unconnected-(U2D-ENET1_RDATA1-PadE7)") (class "Default")
      (node (ref "U2") (pin "E7") (pinfunction "ENET1_RDATA1_E7") (pintype "bidirectional"))
    )
    (net (code "157") (name "unconnected-(U2D-ENET1_RDATA2-PadD7)") (class "Default")
      (node (ref "U2") (pin "D7") (pinfunction "ENET1_RDATA2_D7") (pintype "bidirectional"))
    )
    (net (code "158") (name "unconnected-(U2D-ENET1_RDATA3-PadD16)") (class "Default")
      (node (ref "U2") (pin "D16") (pinfunction "ENET1_RDATA3_D16") (pintype "bidirectional"))
    )
    (net (code "159") (name "unconnected-(U2D-ENET1_RXC-PadF11)") (class "Default")
      (node (ref "U2") (pin "F11") (pinfunction "ENET1_RXC_F11") (pintype "bidirectional"))
    )
    (net (code "160") (name "unconnected-(U2D-ENET1_RX_CLK-PadC6)") (class "Default")
      (node (ref "U2") (pin "C6") (pinfunction "ENET1_RX_CLK_C6") (pintype "bidirectional"))
    )
    (net (code "161") (name "unconnected-(U2D-ENET1_RX_CTL-PadE11)") (class "Default")
      (node (ref "U2") (pin "E11") (pinfunction "ENET1_RX_CTL_E11") (pintype "bidirectional"))
    )
    (net (code "162") (name "unconnected-(U2D-ENET1_TDATA0-PadE13)") (class "Default")
      (node (ref "U2") (pin "E13") (pinfunction "ENET1_TDATA0_E13") (pintype "bidirectional"))
    )
    (net (code "163") (name "unconnected-(U2D-ENET1_TDATA1-PadD13)") (class "Default")
      (node (ref "U2") (pin "D13") (pinfunction "ENET1_TDATA1_D13") (pintype "bidirectional"))
    )
    (net (code "164") (name "unconnected-(U2D-ENET1_TDATA2-PadE16)") (class "Default")
      (node (ref "U2") (pin "E16") (pinfunction "ENET1_TDATA2_E16") (pintype "bidirectional"))
    )
    (net (code "165") (name "unconnected-(U2D-ENET1_TDATA3-PadF16)") (class "Default")
      (node (ref "U2") (pin "F16") (pinfunction "ENET1_TDATA3_F16") (pintype "bidirectional"))
    )
    (net (code "166") (name "unconnected-(U2D-ENET1_TXC-PadG9)") (class "Default")
      (node (ref "U2") (pin "G9") (pinfunction "ENET1_TXC_G9") (pintype "bidirectional"))
    )
    (net (code "167") (name "unconnected-(U2D-ENET1_TX_CLK-PadF13)") (class "Default")
      (node (ref "U2") (pin "F13") (pinfunction "ENET1_TX_CLK_F13") (pintype "bidirectional"))
    )
    (net (code "168") (name "unconnected-(U2D-ENET1_TX_CTL-PadG11)") (class "Default")
      (node (ref "U2") (pin "G11") (pinfunction "ENET1_TX_CTL_G11") (pintype "bidirectional"))
    )
    (net (code "169") (name "unconnected-(U2D-LCD1_CLK-PadD20)") (class "Default")
      (node (ref "U2") (pin "D20") (pinfunction "LCD1_CLK_D20") (pintype "bidirectional"))
    )
    (net (code "170") (name "unconnected-(U2D-LCD1_DATA00-PadF22)") (class "Default")
      (node (ref "U2") (pin "F22") (pinfunction "LCD1_DATA00_F22") (pintype "bidirectional"))
    )
    (net (code "171") (name "unconnected-(U2D-LCD1_DATA01-PadF23)") (class "Default")
      (node (ref "U2") (pin "F23") (pinfunction "LCD1_DATA01_F23") (pintype "bidirectional"))
    )
    (net (code "172") (name "unconnected-(U2D-LCD1_DATA02-PadE23)") (class "Default")
      (node (ref "U2") (pin "E23") (pinfunction "LCD1_DATA02_E23") (pintype "bidirectional"))
    )
    (net (code "173") (name "unconnected-(U2D-LCD1_DATA03-PadE22)") (class "Default")
      (node (ref "U2") (pin "E22") (pinfunction "LCD1_DATA03_E22") (pintype "bidirectional"))
    )
    (net (code "174") (name "unconnected-(U2D-LCD1_DATA04-PadD22)") (class "Default")
      (node (ref "U2") (pin "D22") (pinfunction "LCD1_DATA04_D22") (pintype "bidirectional"))
    )
    (net (code "175") (name "unconnected-(U2D-LCD1_DATA05-PadD23)") (class "Default")
      (node (ref "U2") (pin "D23") (pinfunction "LCD1_DATA05_D23") (pintype "bidirectional"))
    )
    (net (code "176") (name "unconnected-(U2D-LCD1_DATA06-PadE18)") (class "Default")
      (node (ref "U2") (pin "E18") (pinfunction "LCD1_DATA06_E18") (pintype "bidirectional"))
    )
    (net (code "177") (name "unconnected-(U2D-LCD1_DATA07-PadD18)") (class "Default")
      (node (ref "U2") (pin "D18") (pinfunction "LCD1_DATA07_D18") (pintype "bidirectional"))
    )
    (net (code "178") (name "unconnected-(U2D-LCD1_DATA08-PadF20)") (class "Default")
      (node (ref "U2") (pin "F20") (pinfunction "LCD1_DATA08_F20") (pintype "bidirectional"))
    )
    (net (code "179") (name "unconnected-(U2D-LCD1_DATA09-PadG20)") (class "Default")
      (node (ref "U2") (pin "G20") (pinfunction "LCD1_DATA09_G20") (pintype "bidirectional"))
    )
    (net (code "180") (name "unconnected-(U2D-LCD1_DATA10-PadA27)") (class "Default")
      (node (ref "U2") (pin "A27") (pinfunction "LCD1_DATA10_A27") (pintype "bidirectional"))
    )
    (net (code "181") (name "unconnected-(U2D-LCD1_DATA11-PadE27)") (class "Default")
      (node (ref "U2") (pin "E27") (pinfunction "LCD1_DATA11_E27") (pintype "bidirectional"))
    )
    (net (code "182") (name "unconnected-(U2D-LCD1_DATA12-PadF27)") (class "Default")
      (node (ref "U2") (pin "F27") (pinfunction "LCD1_DATA12_F27") (pintype "bidirectional"))
    )
    (net (code "183") (name "unconnected-(U2D-LCD1_DATA13-PadE28)") (class "Default")
      (node (ref "U2") (pin "E28") (pinfunction "LCD1_DATA13_E28") (pintype "bidirectional"))
    )
    (net (code "184") (name "unconnected-(U2D-LCD1_DATA14-PadG27)") (class "Default")
      (node (ref "U2") (pin "G27") (pinfunction "LCD1_DATA14_G27") (pintype "bidirectional"))
    )
    (net (code "185") (name "unconnected-(U2D-LCD1_DATA15-PadB28)") (class "Default")
      (node (ref "U2") (pin "B28") (pinfunction "LCD1_DATA15_B28") (pintype "bidirectional"))
    )
    (net (code "186") (name "unconnected-(U2D-LCD1_DATA16-PadC27)") (class "Default")
      (node (ref "U2") (pin "C27") (pinfunction "LCD1_DATA16_C27") (pintype "bidirectional"))
    )
    (net (code "187") (name "unconnected-(U2D-LCD1_DATA17-PadD26)") (class "Default")
      (node (ref "U2") (pin "D26") (pinfunction "LCD1_DATA17_D26") (pintype "bidirectional"))
    )
    (net (code "188") (name "unconnected-(U2D-LCD1_DATA18-PadD27)") (class "Default")
      (node (ref "U2") (pin "D27") (pinfunction "LCD1_DATA18_D27") (pintype "bidirectional"))
    )
    (net (code "189") (name "unconnected-(U2D-LCD1_DATA19-PadD28)") (class "Default")
      (node (ref "U2") (pin "D28") (pinfunction "LCD1_DATA19_D28") (pintype "bidirectional"))
    )
    (net (code "190") (name "unconnected-(U2D-LCD1_DATA20-PadG26)") (class "Default")
      (node (ref "U2") (pin "G26") (pinfunction "LCD1_DATA20_G26") (pintype "bidirectional"))
    )
    (net (code "191") (name "unconnected-(U2D-LCD1_DATA21-PadH26)") (class "Default")
      (node (ref "U2") (pin "H26") (pinfunction "LCD1_DATA21_H26") (pintype "bidirectional"))
    )
    (net (code "192") (name "unconnected-(U2D-LCD1_DATA22-PadB27)") (class "Default")
      (node (ref "U2") (pin "B27") (pinfunction "LCD1_DATA22_B27") (pintype "bidirectional"))
    )
    (net (code "193") (name "unconnected-(U2D-LCD1_DATA23-PadD25)") (class "Default")
      (node (ref "U2") (pin "D25") (pinfunction "LCD1_DATA23_D25") (pintype "bidirectional"))
    )
    (net (code "194") (name "unconnected-(U2D-LCD1_ENABLE-PadG28)") (class "Default")
      (node (ref "U2") (pin "G28") (pinfunction "LCD1_ENABLE_G28") (pintype "bidirectional"))
    )
    (net (code "195") (name "unconnected-(U2D-LCD1_HSYNC-PadF25)") (class "Default")
      (node (ref "U2") (pin "F25") (pinfunction "LCD1_HSYNC_F25") (pintype "bidirectional"))
    )
    (net (code "196") (name "unconnected-(U2D-LCD1_RESET-PadE20)") (class "Default")
      (node (ref "U2") (pin "E20") (pinfunction "LCD1_RESET_E20") (pintype "bidirectional"))
    )
    (net (code "197") (name "unconnected-(U2D-LCD1_VSYNC-PadF24)") (class "Default")
      (node (ref "U2") (pin "F24") (pinfunction "LCD1_VSYNC_F24") (pintype "bidirectional"))
    )
    (net (code "198") (name "unconnected-(U2D-SAI1_MCLK-PadD3)") (class "Default")
      (node (ref "U2") (pin "D3") (pinfunction "SAI1_MCLK_D3") (pintype "bidirectional"))
    )
    (net (code "199") (name "unconnected-(U2D-SAI1_RXC-PadG4)") (class "Default")
      (node (ref "U2") (pin "G4") (pinfunction "SAI1_RXC_G4") (pintype "bidirectional"))
    )
    (net (code "200") (name "unconnected-(U2D-SAI1_RXD-PadF3)") (class "Default")
      (node (ref "U2") (pin "F3") (pinfunction "SAI1_RXD_F3") (pintype "bidirectional"))
    )
    (net (code "201") (name "unconnected-(U2D-SAI1_RXFS-PadC4)") (class "Default")
      (node (ref "U2") (pin "C4") (pinfunction "SAI1_RXFS_C4") (pintype "bidirectional"))
    )
    (net (code "202") (name "unconnected-(U2D-SAI1_TXC-PadF4)") (class "Default")
      (node (ref "U2") (pin "F4") (pinfunction "SAI1_TXC_F4") (pintype "bidirectional"))
    )
    (net (code "203") (name "unconnected-(U2D-SAI1_TXD-PadG5)") (class "Default")
      (node (ref "U2") (pin "G5") (pinfunction "SAI1_TXD_G5") (pintype "bidirectional"))
    )
    (net (code "204") (name "unconnected-(U2D-SAI1_TXFS-PadF5)") (class "Default")
      (node (ref "U2") (pin "F5") (pinfunction "SAI1_TXFS_F5") (pintype "bidirectional"))
    )
    (net (code "205") (name "unconnected-(U2D-SAI2_RXD-PadE6)") (class "Default")
      (node (ref "U2") (pin "E6") (pinfunction "SAI2_RXD_E6") (pintype "bidirectional"))
    )
    (net (code "206") (name "unconnected-(U2D-SAI2_TXC-PadD4)") (class "Default")
      (node (ref "U2") (pin "D4") (pinfunction "SAI2_TXC_D4") (pintype "bidirectional"))
    )
    (net (code "207") (name "unconnected-(U2D-SAI2_TXD-PadD6)") (class "Default")
      (node (ref "U2") (pin "D6") (pinfunction "SAI2_TXD_D6") (pintype "bidirectional"))
    )
    (net (code "208") (name "unconnected-(U2D-SAI2_TXFS-PadF6)") (class "Default")
      (node (ref "U2") (pin "F6") (pinfunction "SAI2_TXFS_F6") (pintype "bidirectional"))
    )
    (net (code "209") (name "unconnected-(U2E-ADC1_IN0-PadAB7)") (class "Default")
      (node (ref "U2") (pin "AB7") (pinfunction "ADC1_IN0_AB7") (pintype "bidirectional"))
    )
    (net (code "210") (name "unconnected-(U2E-ADC1_IN1-PadAC7)") (class "Default")
      (node (ref "U2") (pin "AC7") (pinfunction "ADC1_IN1_AC7") (pintype "bidirectional"))
    )
    (net (code "211") (name "unconnected-(U2E-ADC1_IN2-PadAD7)") (class "Default")
      (node (ref "U2") (pin "AD7") (pinfunction "ADC1_IN2_AD7") (pintype "bidirectional"))
    )
    (net (code "212") (name "unconnected-(U2E-ADC1_IN3-PadAD9)") (class "Default")
      (node (ref "U2") (pin "AD9") (pinfunction "ADC1_IN3_AD9") (pintype "bidirectional"))
    )
    (net (code "213") (name "unconnected-(U2E-DRAM_~{CS1}-PadAC23)") (class "Default")
      (node (ref "U2") (pin "AC23") (pinfunction "DRAM_~{CS1}_AC23") (pintype "bidirectional"))
    )
    (net (code "214") (name "unconnected-(U2E-EPDC1_BDR0-PadL23)") (class "Default")
      (node (ref "U2") (pin "L23") (pinfunction "EPDC1_BDR0_L23") (pintype "bidirectional"))
    )
    (net (code "215") (name "unconnected-(U2E-EPDC1_BDR1-PadL22)") (class "Default")
      (node (ref "U2") (pin "L22") (pinfunction "EPDC1_BDR1_L22") (pintype "bidirectional"))
    )
    (net (code "216") (name "unconnected-(U2E-EPDC1_DATA05-PadT28)") (class "Default")
      (node (ref "U2") (pin "T28") (pinfunction "EPDC1_DATA05_T28") (pintype "bidirectional"))
    )
    (net (code "217") (name "unconnected-(U2E-EPDC1_DATA06-PadP27)") (class "Default")
      (node (ref "U2") (pin "P27") (pinfunction "EPDC1_DATA06_P27") (pintype "bidirectional"))
    )
    (net (code "218") (name "unconnected-(U2E-EPDC1_DATA07-PadN28)") (class "Default")
      (node (ref "U2") (pin "N28") (pinfunction "EPDC1_DATA07_N28") (pintype "bidirectional"))
    )
    (net (code "219") (name "unconnected-(U2E-EPDC1_DATA08-PadN27)") (class "Default")
      (node (ref "U2") (pin "N27") (pinfunction "EPDC1_DATA08_N27") (pintype "bidirectional"))
    )
    (net (code "220") (name "unconnected-(U2E-EPDC1_DATA09-PadN26)") (class "Default")
      (node (ref "U2") (pin "N26") (pinfunction "EPDC1_DATA09_N26") (pintype "bidirectional"))
    )
    (net (code "221") (name "unconnected-(U2E-EPDC1_DATA10-PadN25)") (class "Default")
      (node (ref "U2") (pin "N25") (pinfunction "EPDC1_DATA10_N25") (pintype "bidirectional"))
    )
    (net (code "222") (name "unconnected-(U2E-EPDC1_DATA11-PadN24)") (class "Default")
      (node (ref "U2") (pin "N24") (pinfunction "EPDC1_DATA11_N24") (pintype "bidirectional"))
    )
    (net (code "223") (name "unconnected-(U2E-EPDC1_DATA12-PadM26)") (class "Default")
      (node (ref "U2") (pin "M26") (pinfunction "EPDC1_DATA12_M26") (pintype "bidirectional"))
    )
    (net (code "224") (name "unconnected-(U2E-EPDC1_DATA13-PadL26)") (class "Default")
      (node (ref "U2") (pin "L26") (pinfunction "EPDC1_DATA13_L26") (pintype "bidirectional"))
    )
    (net (code "225") (name "unconnected-(U2E-EPDC1_DATA14-PadL25)") (class "Default")
      (node (ref "U2") (pin "L25") (pinfunction "EPDC1_DATA14_L25") (pintype "bidirectional"))
    )
    (net (code "226") (name "unconnected-(U2E-EPDC1_DATA15-PadN22)") (class "Default")
      (node (ref "U2") (pin "N22") (pinfunction "EPDC1_DATA15_N22") (pintype "bidirectional"))
    )
    (net (code "227") (name "unconnected-(U2E-EPDC1_GDCLK-PadJ23)") (class "Default")
      (node (ref "U2") (pin "J23") (pinfunction "EPDC1_GDCLK_J23") (pintype "bidirectional"))
    )
    (net (code "228") (name "unconnected-(U2E-EPDC1_GDOE-PadJ22)") (class "Default")
      (node (ref "U2") (pin "J22") (pinfunction "EPDC1_GDOE_J22") (pintype "bidirectional"))
    )
    (net (code "229") (name "unconnected-(U2E-EPDC1_GDRL-PadL24)") (class "Default")
      (node (ref "U2") (pin "L24") (pinfunction "EPDC1_GDRL_L24") (pintype "bidirectional"))
    )
    (net (code "230") (name "unconnected-(U2E-EPDC1_GDSP-PadK27)") (class "Default")
      (node (ref "U2") (pin "K27") (pinfunction "EPDC1_GDSP_K27") (pintype "bidirectional"))
    )
    (net (code "231") (name "unconnected-(U2E-EPDC1_PWRCOM-PadJ27)") (class "Default")
      (node (ref "U2") (pin "J27") (pinfunction "EPDC1_PWRCOM_J27") (pintype "bidirectional"))
    )
    (net (code "232") (name "unconnected-(U2E-EPDC1_PWRSTAT-PadJ26)") (class "Default")
      (node (ref "U2") (pin "J26") (pinfunction "EPDC1_PWRSTAT_J26") (pintype "bidirectional"))
    )
    (net (code "233") (name "unconnected-(U2E-EPDC1_SDCE0-PadJ25)") (class "Default")
      (node (ref "U2") (pin "J25") (pinfunction "EPDC1_SDCE0_J25") (pintype "bidirectional"))
    )
    (net (code "234") (name "unconnected-(U2E-EPDC1_SDCE1-PadJ24)") (class "Default")
      (node (ref "U2") (pin "J24") (pinfunction "EPDC1_SDCE1_J24") (pintype "bidirectional"))
    )
    (net (code "235") (name "unconnected-(U2E-EPDC1_SDCE2-PadG22)") (class "Default")
      (node (ref "U2") (pin "G22") (pinfunction "EPDC1_SDCE2_G22") (pintype "bidirectional"))
    )
    (net (code "236") (name "unconnected-(U2E-EPDC1_SDCE3-PadG23)") (class "Default")
      (node (ref "U2") (pin "G23") (pinfunction "EPDC1_SDCE3_G23") (pintype "bidirectional"))
    )
    (net (code "237") (name "unconnected-(U2E-EPDC1_SDCLK-PadG24)") (class "Default")
      (node (ref "U2") (pin "G24") (pinfunction "EPDC1_SDCLK_G24") (pintype "bidirectional"))
    )
    (net (code "238") (name "unconnected-(U2E-EPDC1_SDLE-PadJ28)") (class "Default")
      (node (ref "U2") (pin "J28") (pinfunction "EPDC1_SDLE_J28") (pintype "bidirectional"))
    )
    (net (code "239") (name "unconnected-(U2E-EPDC1_SDOE-PadG25)") (class "Default")
      (node (ref "U2") (pin "G25") (pinfunction "EPDC1_SDOE_G25") (pintype "bidirectional"))
    )
    (net (code "240") (name "unconnected-(U2E-EPDC1_SDSHR-PadF26)") (class "Default")
      (node (ref "U2") (pin "F26") (pinfunction "EPDC1_SDSHR_F26") (pintype "bidirectional"))
    )
    (net (code "241") (name "unconnected-(U2E-I2C3_SCL-PadT6)") (class "Default")
      (node (ref "U2") (pin "T6") (pinfunction "I2C3_SCL_T6") (pintype "bidirectional"))
    )
    (net (code "242") (name "unconnected-(U2E-I2C3_SDA-PadT7)") (class "Default")
      (node (ref "U2") (pin "T7") (pinfunction "I2C3_SDA_T7") (pintype "bidirectional"))
    )
    (net (code "243") (name "unconnected-(U2E-I2C4_SCL-PadT5)") (class "Default")
      (node (ref "U2") (pin "T5") (pinfunction "I2C4_SCL_T5") (pintype "bidirectional"))
    )
    (net (code "244") (name "unconnected-(U2E-I2C4_SDA-PadT4)") (class "Default")
      (node (ref "U2") (pin "T4") (pinfunction "I2C4_SDA_T4") (pintype "bidirectional"))
    )
    (net (code "245") (name "unconnected-(U2E-SNVS_TAMPER00-PadAE11)") (class "Default")
      (node (ref "U2") (pin "AE11") (pinfunction "SNVS_TAMPER00_AE11") (pintype "bidirectional"))
    )
    (net (code "246") (name "unconnected-(U2E-SNVS_TAMPER01-PadAC11)") (class "Default")
      (node (ref "U2") (pin "AC11") (pinfunction "SNVS_TAMPER01_AC11") (pintype "bidirectional"))
    )
    (net (code "247") (name "unconnected-(U2E-SNVS_TAMPER02-PadAC9)") (class "Default")
      (node (ref "U2") (pin "AC9") (pinfunction "SNVS_TAMPER02_AC9") (pintype "bidirectional"))
    )
    (net (code "248") (name "unconnected-(U2E-SNVS_TAMPER09-PadAB9)") (class "Default")
      (node (ref "U2") (pin "AB9") (pinfunction "SNVS_TAMPER09_AB9") (pintype "bidirectional"))
    )
    (net (code "249") (name "unconnected-(U2E-UART2_RXD-PadT2)") (class "Default")
      (node (ref "U2") (pin "T2") (pinfunction "UART2_RXD_T2") (pintype "bidirectional"))
    )
    (net (code "250") (name "unconnected-(U2E-UART2_TXD-PadT3)") (class "Default")
      (node (ref "U2") (pin "T3") (pinfunction "UART2_TXD_T3") (pintype "bidirectional"))
    )
    (net (code "251") (name "unconnected-(U2E-UART3_CTS-PadV3)") (class "Default")
      (node (ref "U2") (pin "V3") (pinfunction "UART3_CTS_V3") (pintype "bidirectional"))
    )
    (net (code "252") (name "unconnected-(U2E-UART3_RTS-PadW2)") (class "Default")
      (node (ref "U2") (pin "W2") (pinfunction "UART3_RTS_W2") (pintype "bidirectional"))
    )
    (net (code "253") (name "unconnected-(U2E-UART3_RXD-PadV2)") (class "Default")
      (node (ref "U2") (pin "V2") (pinfunction "UART3_RXD_V2") (pintype "bidirectional"))
    )
    (net (code "254") (name "unconnected-(U2E-UART3_TXD-PadU3)") (class "Default")
      (node (ref "U2") (pin "U3") (pinfunction "UART3_TXD_U3") (pintype "bidirectional"))
    )
    (net (code "255") (name "unconnected-(U2F-DRAM_DATA16-PadW27)") (class "Default")
      (node (ref "U2") (pin "W27") (pinfunction "DRAM_DATA16_W27") (pintype "bidirectional"))
    )
    (net (code "256") (name "unconnected-(U2F-DRAM_DATA17-PadY27)") (class "Default")
      (node (ref "U2") (pin "Y27") (pinfunction "DRAM_DATA17_Y27") (pintype "bidirectional"))
    )
    (net (code "257") (name "unconnected-(U2F-DRAM_DATA18-PadY26)") (class "Default")
      (node (ref "U2") (pin "Y26") (pinfunction "DRAM_DATA18_Y26") (pintype "bidirectional"))
    )
    (net (code "258") (name "unconnected-(U2F-DRAM_DATA19-PadY28)") (class "Default")
      (node (ref "U2") (pin "Y28") (pinfunction "DRAM_DATA19_Y28") (pintype "bidirectional"))
    )
    (net (code "259") (name "unconnected-(U2F-DRAM_DATA20-PadAA26)") (class "Default")
      (node (ref "U2") (pin "AA26") (pinfunction "DRAM_DATA20_AA26") (pintype "bidirectional"))
    )
    (net (code "260") (name "unconnected-(U2F-DRAM_DATA21-PadAB26)") (class "Default")
      (node (ref "U2") (pin "AB26") (pinfunction "DRAM_DATA21_AB26") (pintype "bidirectional"))
    )
    (net (code "261") (name "unconnected-(U2F-DRAM_DATA22-PadAB27)") (class "Default")
      (node (ref "U2") (pin "AB27") (pinfunction "DRAM_DATA22_AB27") (pintype "bidirectional"))
    )
    (net (code "262") (name "unconnected-(U2F-DRAM_DATA23-PadAB28)") (class "Default")
      (node (ref "U2") (pin "AB28") (pinfunction "DRAM_DATA23_AB28") (pintype "bidirectional"))
    )
    (net (code "263") (name "unconnected-(U2F-DRAM_DATA24-PadV23)") (class "Default")
      (node (ref "U2") (pin "V23") (pinfunction "DRAM_DATA24_V23") (pintype "bidirectional"))
    )
    (net (code "264") (name "unconnected-(U2F-DRAM_DATA25-PadV22)") (class "Default")
      (node (ref "U2") (pin "V22") (pinfunction "DRAM_DATA25_V22") (pintype "bidirectional"))
    )
    (net (code "265") (name "unconnected-(U2F-DRAM_DATA26-PadT23)") (class "Default")
      (node (ref "U2") (pin "T23") (pinfunction "DRAM_DATA26_T23") (pintype "power_in"))
    )
    (net (code "266") (name "unconnected-(U2F-DRAM_DATA27-PadT22)") (class "Default")
      (node (ref "U2") (pin "T22") (pinfunction "DRAM_DATA27_T22") (pintype "power_in"))
    )
    (net (code "267") (name "unconnected-(U2F-DRAM_DATA28-PadV24)") (class "Default")
      (node (ref "U2") (pin "V24") (pinfunction "DRAM_DATA28_V24") (pintype "bidirectional"))
    )
    (net (code "268") (name "unconnected-(U2F-DRAM_DATA29-PadV25)") (class "Default")
      (node (ref "U2") (pin "V25") (pinfunction "DRAM_DATA29_V25") (pintype "bidirectional"))
    )
    (net (code "269") (name "unconnected-(U2F-DRAM_DATA30-PadT25)") (class "Default")
      (node (ref "U2") (pin "T25") (pinfunction "DRAM_DATA30_T25") (pintype "power_in"))
    )
    (net (code "270") (name "unconnected-(U2F-DRAM_DATA31-PadT24)") (class "Default")
      (node (ref "U2") (pin "T24") (pinfunction "DRAM_DATA31_T24") (pintype "power_in"))
    )
    (net (code "271") (name "unconnected-(U2F-DRAM_DQM2-PadAD28)") (class "Default")
      (node (ref "U2") (pin "AD28") (pinfunction "DRAM_DQM2_AD28") (pintype "bidirectional"))
    )
    (net (code "272") (name "unconnected-(U2F-DRAM_DQM3-PadY25)") (class "Default")
      (node (ref "U2") (pin "Y25") (pinfunction "DRAM_DQM3_Y25") (pintype "bidirectional"))
    )
    (net (code "273") (name "unconnected-(U2F-DRAM_SDQS2_N-PadAD27)") (class "Default")
      (node (ref "U2") (pin "AD27") (pinfunction "DRAM_SDQS2_N_AD27") (pintype "bidirectional"))
    )
    (net (code "274") (name "unconnected-(U2F-DRAM_SDQS2_P-PadAC27)") (class "Default")
      (node (ref "U2") (pin "AC27") (pinfunction "DRAM_SDQS2_P_AC27") (pintype "bidirectional"))
    )
    (net (code "275") (name "unconnected-(U2F-DRAM_SDQS3_N-PadY24)") (class "Default")
      (node (ref "U2") (pin "Y24") (pinfunction "DRAM_SDQS3_N_Y24") (pintype "bidirectional"))
    )
    (net (code "276") (name "unconnected-(U2F-DRAM_SDQS3_P-PadY23)") (class "Default")
      (node (ref "U2") (pin "Y23") (pinfunction "DRAM_SDQS3_P_Y23") (pintype "bidirectional"))
    )
    (net (code "277") (name "unconnected-(U2F-GPIO1_IO13-PadAC5)") (class "Default")
      (node (ref "U2") (pin "AC5") (pinfunction "GPIO1_IO13_AC5") (pintype "bidirectional"))
    )
    (net (code "278") (name "unconnected-(U2F-GPIO1_IO14-PadAC4)") (class "Default")
      (node (ref "U2") (pin "AC4") (pinfunction "GPIO1_IO14_AC4") (pintype "bidirectional"))
    )
    (net (code "279") (name "unconnected-(U2F-GPIO1_IO15-PadAC3)") (class "Default")
      (node (ref "U2") (pin "AC3") (pinfunction "GPIO1_IO15_AC3") (pintype "bidirectional"))
    )
    (net (code "280") (name "unconnected-(U2G-BOOT_MODE0-PadY1)") (class "Default")
      (node (ref "U2") (pin "Y1") (pinfunction "BOOT_MODE0_Y1") (pintype "bidirectional"))
    )
    (net (code "281") (name "unconnected-(U2G-BOOT_MODE1-PadY2)") (class "Default")
      (node (ref "U2") (pin "Y2") (pinfunction "BOOT_MODE1_Y2") (pintype "bidirectional"))
    )
    (net (code "282") (name "unconnected-(U2G-CCM_CLK1_N-PadAE4)") (class "Default")
      (node (ref "U2") (pin "AE4") (pinfunction "CCM_CLK1_N_AE4") (pintype "bidirectional"))
    )
    (net (code "283") (name "unconnected-(U2G-CCM_CLK1_P-PadAE3)") (class "Default")
      (node (ref "U2") (pin "AE3") (pinfunction "CCM_CLK1_P_AE3") (pintype "bidirectional"))
    )
    (net (code "284") (name "unconnected-(U2G-CCM_CLK2-PadAE2)") (class "Default")
      (node (ref "U2") (pin "AE2") (pinfunction "CCM_CLK2_AE2") (pintype "bidirectional"))
    )
    (net (code "285") (name "unconnected-(U2G-DRAM_SDCKE1-PadAB23)") (class "Default")
      (node (ref "U2") (pin "AB23") (pinfunction "DRAM_SDCKE1_AB23") (pintype "bidirectional"))
    )
    (net (code "286") (name "unconnected-(U2G-DRAM_ZQPAD-PadY18)") (class "Default")
      (node (ref "U2") (pin "Y18") (pinfunction "DRAM_ZQPAD_Y18") (pintype "bidirectional"))
    )
    (net (code "287") (name "unconnected-(U2G-FUSE_FSOURCE-PadV9)") (class "Default")
      (node (ref "U2") (pin "V9") (pinfunction "FUSE_FSOURCE_V9") (pintype "power_in"))
    )
    (net (code "288") (name "unconnected-(U2G-GPANAIO-PadAF2)") (class "Default")
      (node (ref "U2") (pin "AF2") (pinfunction "GPANAIO_AF2") (pintype "bidirectional"))
    )
    (net (code "289") (name "unconnected-(U2G-MIPI_VREG_0P4V-PadB19)") (class "Default")
      (node (ref "U2") (pin "B19") (pinfunction "MIPI_VREG_0P4V_B19") (pintype "bidirectional"))
    )
    (net (code "290") (name "unconnected-(U2G-ONOFF-PadAD13)") (class "Default")
      (node (ref "U2") (pin "AD13") (pinfunction "ONOFF_AD13") (pintype "bidirectional"))
    )
    (net (code "291") (name "unconnected-(U2G-PCIE_REFCLKIN_N-PadAG13)") (class "Default")
      (node (ref "U2") (pin "AG13") (pinfunction "PCIE_REFCLKIN_N_AG13") (pintype "bidirectional"))
    )
    (net (code "292") (name "unconnected-(U2G-PCIE_REFCLKIN_P-PadAH13)") (class "Default")
      (node (ref "U2") (pin "AH13") (pinfunction "PCIE_REFCLKIN_P_AH13") (pintype "bidirectional"))
    )
    (net (code "293") (name "unconnected-(U2G-PCIE_REFCLKOUT_N-PadAG11)") (class "Default")
      (node (ref "U2") (pin "AG11") (pinfunction "PCIE_REFCLKOUT_N_AG11") (pintype "bidirectional"))
    )
    (net (code "294") (name "unconnected-(U2G-PCIE_REFCLKOUT_P-PadAH11)") (class "Default")
      (node (ref "U2") (pin "AH11") (pinfunction "PCIE_REFCLKOUT_P_AH11") (pintype "bidirectional"))
    )
    (net (code "295") (name "unconnected-(U2G-PCIE_REXT-PadY16)") (class "Default")
      (node (ref "U2") (pin "Y16") (pinfunction "PCIE_REXT_Y16") (pintype "bidirectional"))
    )
    (net (code "296") (name "unconnected-(U2G-PCIE_RX_N-PadAG16)") (class "Default")
      (node (ref "U2") (pin "AG16") (pinfunction "PCIE_RX_N_AG16") (pintype "bidirectional"))
    )
    (net (code "297") (name "unconnected-(U2G-PCIE_RX_P-PadAH16)") (class "Default")
      (node (ref "U2") (pin "AH16") (pinfunction "PCIE_RX_P_AH16") (pintype "bidirectional"))
    )
    (net (code "298") (name "unconnected-(U2G-PCIE_TX_N-PadAG14)") (class "Default")
      (node (ref "U2") (pin "AG14") (pinfunction "PCIE_TX_N_AG14") (pintype "bidirectional"))
    )
    (net (code "299") (name "unconnected-(U2G-PCIE_TX_P-PadAG15)") (class "Default")
      (node (ref "U2") (pin "AG15") (pinfunction "PCIE_TX_P_AG15") (pintype "bidirectional"))
    )
    (net (code "300") (name "unconnected-(U2G-PCIE_VP-PadAB13)") (class "Default")
      (node (ref "U2") (pin "AB13") (pinfunction "PCIE_VP_AB13") (pintype "bidirectional"))
    )
    (net (code "301") (name "unconnected-(U2G-PCIE_VPH-PadY15)") (class "Default")
      (node (ref "U2") (pin "Y15") (pinfunction "PCIE_VPH_Y15") (pintype "bidirectional"))
    )
    (net (code "302") (name "unconnected-(U2G-PMIC_STBY_REQ-PadAD11)") (class "Default")
      (node (ref "U2") (pin "AD11") (pinfunction "PMIC_STBY_REQ_AD11") (pintype "bidirectional"))
    )
    (net (code "303") (name "unconnected-(U2G-SNVS_PMIC_ON_REQ-PadAE13)") (class "Default")
      (node (ref "U2") (pin "AE13") (pinfunction "SNVS_PMIC_ON_REQ_AE13") (pintype "bidirectional"))
    )
    (net (code "304") (name "unconnected-(U2G-TEMPSENSOR_RESERVE-PadAF6)") (class "Default")
      (node (ref "U2") (pin "AF6") (pinfunction "TEMPSENSOR_RESERVE_AF6") (pintype "bidirectional"))
    )
    (net (code "305") (name "unconnected-(U2G-TEST_MODE-PadAA3)") (class "Default")
      (node (ref "U2") (pin "AA3") (pinfunction "TEST_MODE_AA3") (pintype "bidirectional"))
    )
    (net (code "306") (name "unconnected-(U2G-~{POR}-PadY3)") (class "Default")
      (node (ref "U2") (pin "Y3") (pinfunction "~{POR}_Y3") (pintype "bidirectional"))
    )
  )
)
